# plotter-esp.net
KiCad netlist of a schematic drawn in EasyEDA Pro
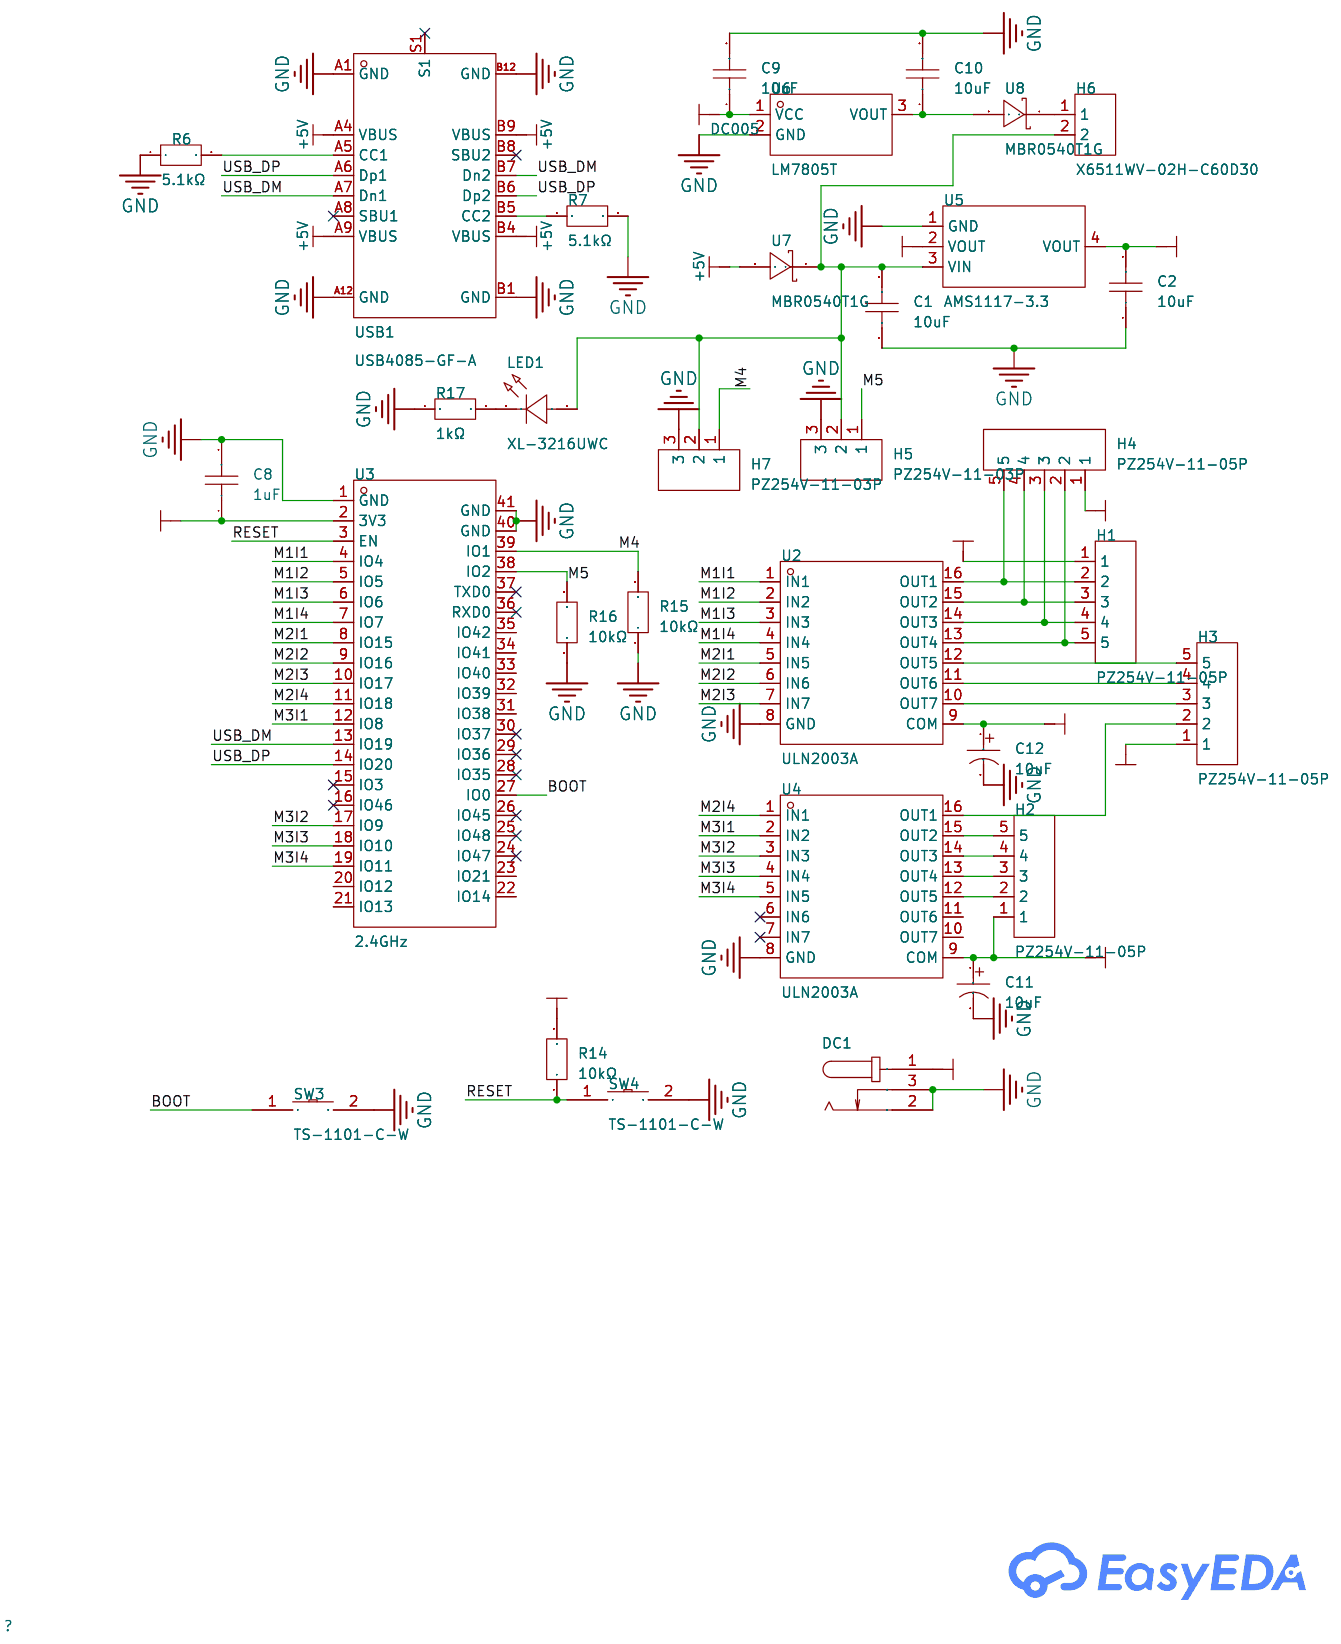
[diagram p0: schematic sheet]

(export (version "E")
  (design (tool "Eeschema 10.0.6"))
  (components
    (comp (ref "C1")
      (value "10uF")
      (footprint "easyedapro:C1206")
      (description "Capacitance:10uF Tolerance:±10% Tolerance:±10% Voltage Rating:25V Temperature Coefficient:X5R")
      (fields
        (field (name "Manufacturer Part") "CL31A106KAHNNNE")
        (field (name "Manufacturer") "SAMSUNG(三星)")
      )
      (libsource (lib "easyedapro") (part "CL31A106KAHNNNE"))
    )
    (comp (ref "C2")
      (value "10uF")
      (footprint "easyedapro:C1206")
      (description "Capacitance:10uF Tolerance:±10% Tolerance:±10% Voltage Rating:25V Temperature Coefficient:X5R")
      (fields
        (field (name "Manufacturer Part") "CL31A106KAHNNNE")
        (field (name "Manufacturer") "SAMSUNG(三星)")
      )
      (libsource (lib "easyedapro") (part "CL31A106KAHNNNE"))
    )
    (comp (ref "C8")
      (value "1uF")
      (footprint "easyedapro:C1206")
      (description "Capacitance:1uF Tolerance:±10% Tolerance:±10% Voltage Rating:50V Temperature Coefficient:X7R")
      (fields
        (field (name "Manufacturer Part") "CL31B105KBHNNNE")
        (field (name "Manufacturer") "SAMSUNG(三星)")
      )
      (libsource (lib "easyedapro") (part "CL31B105KBHNNNE"))
    )
    (comp (ref "C9")
      (value "10uF")
      (footprint "easyedapro:C1206")
      (description "Capacitance:10uF Tolerance:±10% Tolerance:±10% Voltage Rating:25V Temperature Coefficient:X5R")
      (fields
        (field (name "Manufacturer Part") "CL31A106KAHNNNE")
        (field (name "Manufacturer") "SAMSUNG(三星)")
      )
      (libsource (lib "easyedapro") (part "CL31A106KAHNNNE"))
    )
    (comp (ref "C10")
      (value "10uF")
      (footprint "easyedapro:C1206")
      (description "Capacitance:10uF Tolerance:±10% Tolerance:±10% Voltage Rating:25V Temperature Coefficient:X5R")
      (fields
        (field (name "Manufacturer Part") "CL31A106KAHNNNE")
        (field (name "Manufacturer") "SAMSUNG(三星)")
      )
      (libsource (lib "easyedapro") (part "CL31A106KAHNNNE"))
    )
    (comp (ref "C11")
      (value "10uF")
      (footprint "easyedapro:CAP-TH_BD4.0-P1.50-D0.8-FD")
      (fields
        (field (name "Manufacturer Part") "KF106M025C05RR0VH2FP0")
        (field (name "Manufacturer") "Chengx(承兴)")
      )
      (libsource (lib "easyedapro") (part "10uF 25V 4*5"))
    )
    (comp (ref "C12")
      (value "10uF")
      (footprint "easyedapro:CAP-TH_BD4.0-P1.50-D0.8-FD")
      (fields
        (field (name "Manufacturer Part") "KF106M025C05RR0VH2FP0")
        (field (name "Manufacturer") "Chengx(承兴)")
      )
      (libsource (lib "easyedapro") (part "10uF 25V 4*5"))
    )
    (comp (ref "DC1")
      (value "DC005")
      (footprint "easyedapro:DC-IN-TH_DC005")
      (fields (field (name "Manufacturer") "SHOU HAN(首韩)"))
      (libsource (lib "easyedapro") (part "DC005_C431533"))
    )
    (comp (ref "H1")
      (value "PZ254V-11-05P")
      (footprint "easyedapro:HDR-TH_5P-P2.54-V-M")
      (fields (field (name "Manufacturer") "XFCN(兴飞)"))
      (libsource (lib "easyedapro") (part "PZ254V-11-05P"))
    )
    (comp (ref "H2")
      (value "PZ254V-11-05P")
      (footprint "easyedapro:HDR-TH_5P-P2.54-V-M")
      (fields (field (name "Manufacturer") "XFCN(兴飞)"))
      (libsource (lib "easyedapro") (part "PZ254V-11-05P"))
    )
    (comp (ref "H3")
      (value "PZ254V-11-05P")
      (footprint "easyedapro:HDR-TH_5P-P2.54-V-M")
      (fields (field (name "Manufacturer") "XFCN(兴飞)"))
      (libsource (lib "easyedapro") (part "PZ254V-11-05P"))
    )
    (comp (ref "H4")
      (value "PZ254V-11-05P")
      (footprint "easyedapro:HDR-TH_5P-P2.54-V-M")
      (fields (field (name "Manufacturer") "XFCN(兴飞)"))
      (libsource (lib "easyedapro") (part "PZ254V-11-05P"))
    )
    (comp (ref "H5")
      (value "PZ254V-11-03P")
      (footprint "easyedapro:HDR-TH_3P-P2.54-V-M_PZ254V-11-03P")
      (fields (field (name "Manufacturer") "XFCN(兴飞)"))
      (libsource (lib "easyedapro") (part "PZ254V-11-03P_C2937625"))
    )
    (comp (ref "H6")
      (value "X6511WV-02H-C60D30")
      (footprint "easyedapro:HDR-TH_2P-P2.54-V-M")
      (fields (field (name "Manufacturer") "XKB Connection(中国星坤)"))
      (libsource (lib "easyedapro") (part "X6511WV-02H-C30D60"))
    )
    (comp (ref "H7")
      (value "PZ254V-11-03P")
      (footprint "easyedapro:HDR-TH_3P-P2.54-V-M_PZ254V-11-03P")
      (fields (field (name "Manufacturer") "XFCN(兴飞)"))
      (libsource (lib "easyedapro") (part "PZ254V-11-03P_C2937625"))
    )
    (comp (ref "LED1")
      (value "XL-3216UWC")
      (footprint "easyedapro:LED1206-R-RD_WHITE")
      (fields (field (name "Manufacturer") "XINGLIGHT(成兴光)"))
      (libsource (lib "easyedapro") (part "XL-3216UWC"))
    )
    (comp (ref "R6")
      (value "5.1kΩ")
      (footprint "easyedapro:R1206")
      (fields (field (name "Manufacturer Part") "FRC1206J512 TS") (field (name "Manufacturer") "FOJAN(富捷)"))
      (libsource (lib "easyedapro") (part "FRC1206J512 TS"))
    )
    (comp (ref "R7")
      (value "5.1kΩ")
      (footprint "easyedapro:R1206")
      (fields (field (name "Manufacturer Part") "FRC1206J512 TS") (field (name "Manufacturer") "FOJAN(富捷)"))
      (libsource (lib "easyedapro") (part "FRC1206J512 TS"))
    )
    (comp (ref "R14")
      (value "10kΩ")
      (footprint "easyedapro:R1206")
      (fields (field (name "Manufacturer Part") "FRC1206J103 TS") (field (name "Manufacturer") "FOJAN(富捷)"))
      (libsource (lib "easyedapro") (part "FRC1206J103 TS"))
    )
    (comp (ref "R15")
      (value "10kΩ")
      (footprint "easyedapro:R1206")
      (fields (field (name "Manufacturer Part") "FRC1206J103 TS") (field (name "Manufacturer") "FOJAN(富捷)"))
      (libsource (lib "easyedapro") (part "FRC1206J103 TS"))
    )
    (comp (ref "R16")
      (value "10kΩ")
      (footprint "easyedapro:R1206")
      (fields (field (name "Manufacturer Part") "FRC1206J103 TS") (field (name "Manufacturer") "FOJAN(富捷)"))
      (libsource (lib "easyedapro") (part "FRC1206J103 TS"))
    )
    (comp (ref "R17")
      (value "1kΩ")
      (footprint "easyedapro:R1206")
      (fields (field (name "Manufacturer Part") "FRC1206J102 TS") (field (name "Manufacturer") "FOJAN(富捷)"))
      (libsource (lib "easyedapro") (part "FRC1206J102 TS"))
    )
    (comp (ref "SW3")
      (value "TS-1101-C-W")
      (footprint "easyedapro:SW-SMD_L6.0-W3.3-LS8.0")
      (fields (field (name "Manufacturer") "XKB Connectivity(中国星坤)"))
      (libsource (lib "easyedapro") (part "TS-1101-C-W"))
    )
    (comp (ref "SW4")
      (value "TS-1101-C-W")
      (footprint "easyedapro:SW-SMD_L6.0-W3.3-LS8.0")
      (fields (field (name "Manufacturer") "XKB Connectivity(中国星坤)"))
      (libsource (lib "easyedapro") (part "TS-1101-C-W"))
    )
    (comp (ref "U2")
      (value "ULN2003A")
      (footprint "easyedapro:DIP-16_L20.0-W6.4-P2.54-LS7.6-BL")
      (fields (field (name "Manufacturer") "ST(意法半导体)"))
      (libsource (lib "easyedapro") (part "ULN2003A_C93000"))
    )
    (comp (ref "U3")
      (value "2.4GHz")
      (footprint "easyedapro:WIRELM-SMD_ESP32-S3-WROOM-1U")
      (fields
        (field (name "Manufacturer Part") "ESP32-S3-WROOM-1U-N4R8")
        (field (name "Manufacturer") "ESPRESSIF(乐鑫)")
      )
      (libsource (lib "easyedapro") (part "ESP32-S3-WROOM-1U-N4R8"))
    )
    (comp (ref "U4")
      (value "ULN2003A")
      (footprint "easyedapro:DIP-16_L20.0-W6.4-P2.54-LS7.6-BL")
      (fields (field (name "Manufacturer") "ST(意法半导体)"))
      (libsource (lib "easyedapro") (part "ULN2003A_C93000"))
    )
    (comp (ref "U5")
      (value "AMS1117-3.3")
      (footprint "easyedapro:SOT-223-3_L6.5-W3.4-P2.30-LS7.0-BR")
      (fields (field (name "Manufacturer") "AMS"))
      (libsource (lib "easyedapro") (part "AMS1117-3.3"))
    )
    (comp (ref "U6")
      (value "LM7805T")
      (footprint "easyedapro:TO-220-3_L10.1-W4.7-P2.54-L")
      (fields (field (name "Manufacturer") "HGSEMI(华冠)"))
      (libsource (lib "easyedapro") (part "LM7805T_C7432180"))
    )
    (comp (ref "U7")
      (value "MBR0540T1G")
      (footprint "easyedapro:SOD-123_L2.8-W1.8-LS3.7-RD")
      (fields (field (name "Manufacturer") "HXY MOSFET(华轩阳电子)"))
      (libsource (lib "easyedapro") (part "MBR0540T1G_C20611940"))
    )
    (comp (ref "U8")
      (value "MBR0540T1G")
      (footprint "easyedapro:SOD-123_L2.8-W1.8-LS3.7-RD")
      (fields (field (name "Manufacturer") "HXY MOSFET(华轩阳电子)"))
      (libsource (lib "easyedapro") (part "MBR0540T1G_C20611940"))
    )
    (comp (ref "USB1")
      (value "USB4085-GF-A")
      (footprint "easyedapro:USC-C-SMD_USB4085-GF-A")
      (fields (field (name "Manufacturer") "GCT"))
      (libsource (lib "easyedapro") (part "USB4085-GF-A_C7095263"))
    )
  )
  (nets
    (net (code "1") (name "+3V3") (class "Default")
      (node (ref "C2") (pin "2") (pinfunction "2_2") (pintype "unspecified"))
      (node (ref "C8") (pin "1") (pinfunction "1_1") (pintype "unspecified"))
      (node (ref "R14") (pin "2") (pinfunction "2_2") (pintype "unspecified"))
      (node (ref "U3") (pin "2") (pinfunction "3V3_2") (pintype "unspecified"))
      (node (ref "U5") (pin "2") (pinfunction "VOUT_2") (pintype "unspecified"))
      (node (ref "U5") (pin "4") (pinfunction "VOUT_4") (pintype "unspecified"))
    )
    (net (code "2") (name "+5V") (class "Default")
      (node (ref "U7") (pin "2") (pinfunction "A_2") (pintype "unspecified"))
      (node (ref "USB1") (pin "A4") (pinfunction "VBUS_A4") (pintype "unspecified"))
      (node (ref "USB1") (pin "A9") (pinfunction "VBUS_A9") (pintype "unspecified"))
      (node (ref "USB1") (pin "B4") (pinfunction "VBUS_B4") (pintype "unspecified"))
      (node (ref "USB1") (pin "B9") (pinfunction "VBUS_B9") (pintype "unspecified"))
    )
    (net (code "3") (name "+12V") (class "Default")
      (node (ref "C11") (pin "1") (pinfunction "1_1") (pintype "input"))
      (node (ref "C12") (pin "1") (pinfunction "1_1") (pintype "input"))
      (node (ref "C9") (pin "1") (pinfunction "1_1") (pintype "unspecified"))
      (node (ref "DC1") (pin "1") (pinfunction "1_1") (pintype "unspecified"))
      (node (ref "H1") (pin "1") (pinfunction "1_1") (pintype "unspecified"))
      (node (ref "H2") (pin "1") (pinfunction "1_1") (pintype "unspecified"))
      (node (ref "H3") (pin "1") (pinfunction "1_1") (pintype "unspecified"))
      (node (ref "H4") (pin "1") (pinfunction "1_1") (pintype "unspecified"))
      (node (ref "U2") (pin "9") (pinfunction "COM_9") (pintype "unspecified"))
      (node (ref "U4") (pin "9") (pinfunction "COM_9") (pintype "unspecified"))
      (node (ref "U6") (pin "1") (pinfunction "VCC_1") (pintype "unspecified"))
    )
    (net (code "4") (name "/BOOT") (class "Default")
      (node (ref "SW3") (pin "1") (pinfunction "1_1") (pintype "unspecified"))
      (node (ref "U3") (pin "27") (pinfunction "IO0_27") (pintype "unspecified"))
    )
    (net (code "5") (name "/M1I1") (class "Default")
      (node (ref "U2") (pin "1") (pinfunction "IN1_1") (pintype "unspecified"))
      (node (ref "U3") (pin "4") (pinfunction "IO4_4") (pintype "unspecified"))
    )
    (net (code "6") (name "/M1I2") (class "Default")
      (node (ref "U2") (pin "2") (pinfunction "IN2_2") (pintype "unspecified"))
      (node (ref "U3") (pin "5") (pinfunction "IO5_5") (pintype "unspecified"))
    )
    (net (code "7") (name "/M1I3") (class "Default")
      (node (ref "U2") (pin "3") (pinfunction "IN3_3") (pintype "unspecified"))
      (node (ref "U3") (pin "6") (pinfunction "IO6_6") (pintype "unspecified"))
    )
    (net (code "8") (name "/M1I4") (class "Default")
      (node (ref "U2") (pin "4") (pinfunction "IN4_4") (pintype "unspecified"))
      (node (ref "U3") (pin "7") (pinfunction "IO7_7") (pintype "unspecified"))
    )
    (net (code "9") (name "/M2I1") (class "Default")
      (node (ref "U2") (pin "5") (pinfunction "IN5_5") (pintype "unspecified"))
      (node (ref "U3") (pin "8") (pinfunction "IO15_8") (pintype "unspecified"))
    )
    (net (code "10") (name "/M2I2") (class "Default")
      (node (ref "U2") (pin "6") (pinfunction "IN6_6") (pintype "unspecified"))
      (node (ref "U3") (pin "9") (pinfunction "IO16_9") (pintype "unspecified"))
    )
    (net (code "11") (name "/M2I3") (class "Default")
      (node (ref "U2") (pin "7") (pinfunction "IN7_7") (pintype "unspecified"))
      (node (ref "U3") (pin "10") (pinfunction "IO17_10") (pintype "unspecified"))
    )
    (net (code "12") (name "/M2I4") (class "Default")
      (node (ref "U3") (pin "11") (pinfunction "IO18_11") (pintype "unspecified"))
      (node (ref "U4") (pin "1") (pinfunction "IN1_1") (pintype "unspecified"))
    )
    (net (code "13") (name "/M3I1") (class "Default")
      (node (ref "U3") (pin "12") (pinfunction "IO8_12") (pintype "unspecified"))
      (node (ref "U4") (pin "2") (pinfunction "IN2_2") (pintype "unspecified"))
    )
    (net (code "14") (name "/M3I2") (class "Default")
      (node (ref "U3") (pin "17") (pinfunction "IO9_17") (pintype "unspecified"))
      (node (ref "U4") (pin "3") (pinfunction "IN3_3") (pintype "unspecified"))
    )
    (net (code "15") (name "/M3I3") (class "Default")
      (node (ref "U3") (pin "18") (pinfunction "IO10_18") (pintype "unspecified"))
      (node (ref "U4") (pin "4") (pinfunction "IN4_4") (pintype "unspecified"))
    )
    (net (code "16") (name "/M3I4") (class "Default")
      (node (ref "U3") (pin "19") (pinfunction "IO11_19") (pintype "unspecified"))
      (node (ref "U4") (pin "5") (pinfunction "IN5_5") (pintype "unspecified"))
    )
    (net (code "17") (name "/M4") (class "Default")
      (node (ref "H7") (pin "1") (pinfunction "1_1") (pintype "unspecified"))
      (node (ref "R15") (pin "2") (pinfunction "2_2") (pintype "unspecified"))
      (node (ref "U3") (pin "39") (pinfunction "IO1_39") (pintype "unspecified"))
    )
    (net (code "18") (name "/M5") (class "Default")
      (node (ref "H5") (pin "1") (pinfunction "1_1") (pintype "unspecified"))
      (node (ref "R16") (pin "2") (pinfunction "2_2") (pintype "unspecified"))
      (node (ref "U3") (pin "38") (pinfunction "IO2_38") (pintype "unspecified"))
    )
    (net (code "19") (name "/RESET") (class "Default")
      (node (ref "R14") (pin "1") (pinfunction "1_1") (pintype "unspecified"))
      (node (ref "SW4") (pin "1") (pinfunction "1_1") (pintype "unspecified"))
      (node (ref "U3") (pin "3") (pinfunction "EN_3") (pintype "unspecified"))
    )
    (net (code "20") (name "/USB_DM") (class "Default")
      (node (ref "U3") (pin "13") (pinfunction "IO19_13") (pintype "unspecified"))
      (node (ref "USB1") (pin "A7") (pinfunction "Dn1_A7") (pintype "unspecified"))
      (node (ref "USB1") (pin "B7") (pinfunction "Dn2_B7") (pintype "unspecified"))
    )
    (net (code "21") (name "/USB_DP") (class "Default")
      (node (ref "U3") (pin "14") (pinfunction "IO20_14") (pintype "unspecified"))
      (node (ref "USB1") (pin "A6") (pinfunction "Dp1_A6") (pintype "unspecified"))
      (node (ref "USB1") (pin "B6") (pinfunction "Dp2_B6") (pintype "unspecified"))
    )
    (net (code "22") (name "GND") (class "Default")
      (node (ref "C1") (pin "1") (pinfunction "1_1") (pintype "unspecified"))
      (node (ref "C10") (pin "2") (pinfunction "2_2") (pintype "unspecified"))
      (node (ref "C11") (pin "2") (pinfunction "2_2") (pintype "input"))
      (node (ref "C12") (pin "2") (pinfunction "2_2") (pintype "input"))
      (node (ref "C2") (pin "1") (pinfunction "1_1") (pintype "unspecified"))
      (node (ref "C8") (pin "2") (pinfunction "2_2") (pintype "unspecified"))
      (node (ref "C9") (pin "2") (pinfunction "2_2") (pintype "unspecified"))
      (node (ref "DC1") (pin "2") (pinfunction "2_2") (pintype "unspecified"))
      (node (ref "DC1") (pin "3") (pinfunction "3_3") (pintype "unspecified"))
      (node (ref "H5") (pin "3") (pinfunction "3_3") (pintype "unspecified"))
      (node (ref "H7") (pin "3") (pinfunction "3_3") (pintype "unspecified"))
      (node (ref "R15") (pin "1") (pinfunction "1_1") (pintype "unspecified"))
      (node (ref "R16") (pin "1") (pinfunction "1_1") (pintype "unspecified"))
      (node (ref "R17") (pin "1") (pinfunction "1_1") (pintype "unspecified"))
      (node (ref "R6") (pin "1") (pinfunction "1_1") (pintype "unspecified"))
      (node (ref "R7") (pin "2") (pinfunction "2_2") (pintype "unspecified"))
      (node (ref "SW3") (pin "2") (pinfunction "2_2") (pintype "unspecified"))
      (node (ref "SW4") (pin "2") (pinfunction "2_2") (pintype "unspecified"))
      (node (ref "U2") (pin "8") (pinfunction "GND_8") (pintype "unspecified"))
      (node (ref "U3") (pin "1") (pinfunction "GND_1") (pintype "unspecified"))
      (node (ref "U3") (pin "40") (pinfunction "GND_40") (pintype "unspecified"))
      (node (ref "U3") (pin "41") (pinfunction "GND_41") (pintype "unspecified"))
      (node (ref "U4") (pin "8") (pinfunction "GND_8") (pintype "unspecified"))
      (node (ref "U5") (pin "1") (pinfunction "GND_1") (pintype "unspecified"))
      (node (ref "U6") (pin "2") (pinfunction "GND_2") (pintype "unspecified"))
      (node (ref "USB1") (pin "A1") (pinfunction "GND_A1") (pintype "unspecified"))
      (node (ref "USB1") (pin "A12") (pinfunction "GND_A12") (pintype "unspecified"))
      (node (ref "USB1") (pin "B1") (pinfunction "GND_B1") (pintype "unspecified"))
      (node (ref "USB1") (pin "B12") (pinfunction "GND_B12") (pintype "unspecified"))
    )
    (net (code "23") (name "Net-(LED1-A)") (class "Default")
      (node (ref "C1") (pin "2") (pinfunction "2_2") (pintype "unspecified"))
      (node (ref "H5") (pin "2") (pinfunction "2_2") (pintype "unspecified"))
      (node (ref "H6") (pin "2") (pinfunction "2_2") (pintype "unspecified"))
      (node (ref "H7") (pin "2") (pinfunction "2_2") (pintype "unspecified"))
      (node (ref "LED1") (pin "1") (pinfunction "A_1") (pintype "unspecified"))
      (node (ref "U5") (pin "3") (pinfunction "VIN_3") (pintype "unspecified"))
      (node (ref "U7") (pin "1") (pinfunction "K_1") (pintype "unspecified"))
    )
    (net (code "24") (name "Net-(LED1-K)") (class "Default")
      (node (ref "LED1") (pin "2") (pinfunction "K_2") (pintype "unspecified"))
      (node (ref "R17") (pin "2") (pinfunction "2_2") (pintype "unspecified"))
    )
    (net (code "25") (name "Net-(U2-OUT1)") (class "Default")
      (node (ref "H1") (pin "2") (pinfunction "2_2") (pintype "unspecified"))
      (node (ref "H4") (pin "5") (pinfunction "5_5") (pintype "unspecified"))
      (node (ref "U2") (pin "16") (pinfunction "OUT1_16") (pintype "unspecified"))
    )
    (net (code "26") (name "Net-(U2-OUT2)") (class "Default")
      (node (ref "H1") (pin "3") (pinfunction "3_3") (pintype "unspecified"))
      (node (ref "H4") (pin "4") (pinfunction "4_4") (pintype "unspecified"))
      (node (ref "U2") (pin "15") (pinfunction "OUT2_15") (pintype "unspecified"))
    )
    (net (code "27") (name "Net-(U2-OUT3)") (class "Default")
      (node (ref "H1") (pin "4") (pinfunction "4_4") (pintype "unspecified"))
      (node (ref "H4") (pin "3") (pinfunction "3_3") (pintype "unspecified"))
      (node (ref "U2") (pin "14") (pinfunction "OUT3_14") (pintype "unspecified"))
    )
    (net (code "28") (name "Net-(U2-OUT4)") (class "Default")
      (node (ref "H1") (pin "5") (pinfunction "5_5") (pintype "unspecified"))
      (node (ref "H4") (pin "2") (pinfunction "2_2") (pintype "unspecified"))
      (node (ref "U2") (pin "13") (pinfunction "OUT4_13") (pintype "unspecified"))
    )
    (net (code "29") (name "Net-(U2-OUT5)") (class "Default")
      (node (ref "H3") (pin "5") (pinfunction "5_5") (pintype "unspecified"))
      (node (ref "U2") (pin "12") (pinfunction "OUT5_12") (pintype "unspecified"))
    )
    (net (code "30") (name "Net-(U2-OUT6)") (class "Default")
      (node (ref "H3") (pin "4") (pinfunction "4_4") (pintype "unspecified"))
      (node (ref "U2") (pin "11") (pinfunction "OUT6_11") (pintype "unspecified"))
    )
    (net (code "31") (name "Net-(U2-OUT7)") (class "Default")
      (node (ref "H3") (pin "3") (pinfunction "3_3") (pintype "unspecified"))
      (node (ref "U2") (pin "10") (pinfunction "OUT7_10") (pintype "unspecified"))
    )
    (net (code "32") (name "Net-(U4-OUT1)") (class "Default")
      (node (ref "H3") (pin "2") (pinfunction "2_2") (pintype "unspecified"))
      (node (ref "U4") (pin "16") (pinfunction "OUT1_16") (pintype "unspecified"))
    )
    (net (code "33") (name "Net-(U4-OUT2)") (class "Default")
      (node (ref "H2") (pin "5") (pinfunction "5_5") (pintype "unspecified"))
      (node (ref "U4") (pin "15") (pinfunction "OUT2_15") (pintype "unspecified"))
    )
    (net (code "34") (name "Net-(U4-OUT3)") (class "Default")
      (node (ref "H2") (pin "4") (pinfunction "4_4") (pintype "unspecified"))
      (node (ref "U4") (pin "14") (pinfunction "OUT3_14") (pintype "unspecified"))
    )
    (net (code "35") (name "Net-(U4-OUT4)") (class "Default")
      (node (ref "H2") (pin "3") (pinfunction "3_3") (pintype "unspecified"))
      (node (ref "U4") (pin "13") (pinfunction "OUT4_13") (pintype "unspecified"))
    )
    (net (code "36") (name "Net-(U4-OUT5)") (class "Default")
      (node (ref "H2") (pin "2") (pinfunction "2_2") (pintype "unspecified"))
      (node (ref "U4") (pin "12") (pinfunction "OUT5_12") (pintype "unspecified"))
    )
    (net (code "37") (name "Net-(U6-VOUT)") (class "Default")
      (node (ref "C10") (pin "1") (pinfunction "1_1") (pintype "unspecified"))
      (node (ref "U6") (pin "3") (pinfunction "VOUT_3") (pintype "unspecified"))
      (node (ref "U8") (pin "2") (pinfunction "A_2") (pintype "unspecified"))
    )
    (net (code "38") (name "Net-(U8-K)") (class "Default")
      (node (ref "H6") (pin "1") (pinfunction "1_1") (pintype "unspecified"))
      (node (ref "U8") (pin "1") (pinfunction "K_1") (pintype "unspecified"))
    )
    (net (code "39") (name "Net-(USB1-CC1)") (class "Default")
      (node (ref "R6") (pin "2") (pinfunction "2_2") (pintype "unspecified"))
      (node (ref "USB1") (pin "A5") (pinfunction "CC1_A5") (pintype "unspecified"))
    )
    (net (code "40") (name "Net-(USB1-CC2)") (class "Default")
      (node (ref "R7") (pin "1") (pinfunction "1_1") (pintype "unspecified"))
      (node (ref "USB1") (pin "B5") (pinfunction "CC2_B5") (pintype "unspecified"))
    )
    (net (code "41") (name "unconnected-(U3-IO3-Pad15)") (class "Default")
      (node (ref "U3") (pin "15") (pinfunction "IO3_15") (pintype "unspecified+no_connect"))
    )
    (net (code "42") (name "unconnected-(U3-IO12-Pad20)") (class "Default")
      (node (ref "U3") (pin "20") (pinfunction "IO12_20") (pintype "unspecified"))
    )
    (net (code "43") (name "unconnected-(U3-IO13-Pad21)") (class "Default")
      (node (ref "U3") (pin "21") (pinfunction "IO13_21") (pintype "unspecified"))
    )
    (net (code "44") (name "unconnected-(U3-IO14-Pad22)") (class "Default")
      (node (ref "U3") (pin "22") (pinfunction "IO14_22") (pintype "unspecified"))
    )
    (net (code "45") (name "unconnected-(U3-IO21-Pad23)") (class "Default")
      (node (ref "U3") (pin "23") (pinfunction "IO21_23") (pintype "unspecified"))
    )
    (net (code "46") (name "unconnected-(U3-IO35-Pad28)") (class "Default")
      (node (ref "U3") (pin "28") (pinfunction "IO35_28") (pintype "unspecified+no_connect"))
    )
    (net (code "47") (name "unconnected-(U3-IO36-Pad29)") (class "Default")
      (node (ref "U3") (pin "29") (pinfunction "IO36_29") (pintype "unspecified+no_connect"))
    )
    (net (code "48") (name "unconnected-(U3-IO37-Pad30)") (class "Default")
      (node (ref "U3") (pin "30") (pinfunction "IO37_30") (pintype "unspecified+no_connect"))
    )
    (net (code "49") (name "unconnected-(U3-IO38-Pad31)") (class "Default")
      (node (ref "U3") (pin "31") (pinfunction "IO38_31") (pintype "unspecified"))
    )
    (net (code "50") (name "unconnected-(U3-IO39-Pad32)") (class "Default")
      (node (ref "U3") (pin "32") (pinfunction "IO39_32") (pintype "unspecified"))
    )
    (net (code "51") (name "unconnected-(U3-IO40-Pad33)") (class "Default")
      (node (ref "U3") (pin "33") (pinfunction "IO40_33") (pintype "unspecified"))
    )
    (net (code "52") (name "unconnected-(U3-IO41-Pad34)") (class "Default")
      (node (ref "U3") (pin "34") (pinfunction "IO41_34") (pintype "unspecified"))
    )
    (net (code "53") (name "unconnected-(U3-IO42-Pad35)") (class "Default")
      (node (ref "U3") (pin "35") (pinfunction "IO42_35") (pintype "unspecified"))
    )
    (net (code "54") (name "unconnected-(U3-IO45-Pad26)") (class "Default")
      (node (ref "U3") (pin "26") (pinfunction "IO45_26") (pintype "unspecified+no_connect"))
    )
    (net (code "55") (name "unconnected-(U3-IO46-Pad16)") (class "Default")
      (node (ref "U3") (pin "16") (pinfunction "IO46_16") (pintype "unspecified+no_connect"))
    )
    (net (code "56") (name "unconnected-(U3-IO47-Pad24)") (class "Default")
      (node (ref "U3") (pin "24") (pinfunction "IO47_24") (pintype "unspecified+no_connect"))
    )
    (net (code "57") (name "unconnected-(U3-IO48-Pad25)") (class "Default")
      (node (ref "U3") (pin "25") (pinfunction "IO48_25") (pintype "unspecified+no_connect"))
    )
    (net (code "58") (name "unconnected-(U3-RXD0-Pad36)") (class "Default")
      (node (ref "U3") (pin "36") (pinfunction "RXD0_36") (pintype "unspecified+no_connect"))
    )
    (net (code "59") (name "unconnected-(U3-TXD0-Pad37)") (class "Default")
      (node (ref "U3") (pin "37") (pinfunction "TXD0_37") (pintype "unspecified+no_connect"))
    )
    (net (code "60") (name "unconnected-(U4-IN6-Pad6)") (class "Default")
      (node (ref "U4") (pin "6") (pinfunction "IN6_6") (pintype "unspecified+no_connect"))
    )
    (net (code "61") (name "unconnected-(U4-IN7-Pad7)") (class "Default")
      (node (ref "U4") (pin "7") (pinfunction "IN7_7") (pintype "unspecified+no_connect"))
    )
    (net (code "62") (name "unconnected-(U4-OUT6-Pad11)") (class "Default")
      (node (ref "U4") (pin "11") (pinfunction "OUT6_11") (pintype "unspecified"))
    )
    (net (code "63") (name "unconnected-(U4-OUT7-Pad10)") (class "Default")
      (node (ref "U4") (pin "10") (pinfunction "OUT7_10") (pintype "unspecified"))
    )
    (net (code "64") (name "unconnected-(USB1-PadS1)") (class "Default")
      (node (ref "USB1") (pin "S1") (pinfunction "S1_S1") (pintype "unspecified+no_connect"))
    )
    (net (code "65") (name "unconnected-(USB1-SBU1-PadA8)") (class "Default")
      (node (ref "USB1") (pin "A8") (pinfunction "SBU1_A8") (pintype "unspecified+no_connect"))
    )
    (net (code "66") (name "unconnected-(USB1-SBU2-PadB8)") (class "Default")
      (node (ref "USB1") (pin "B8") (pinfunction "SBU2_B8") (pintype "unspecified+no_connect"))
    )
  )
)
